# biggity.net
KiCad netlist of a schematic drawn in EAGLE
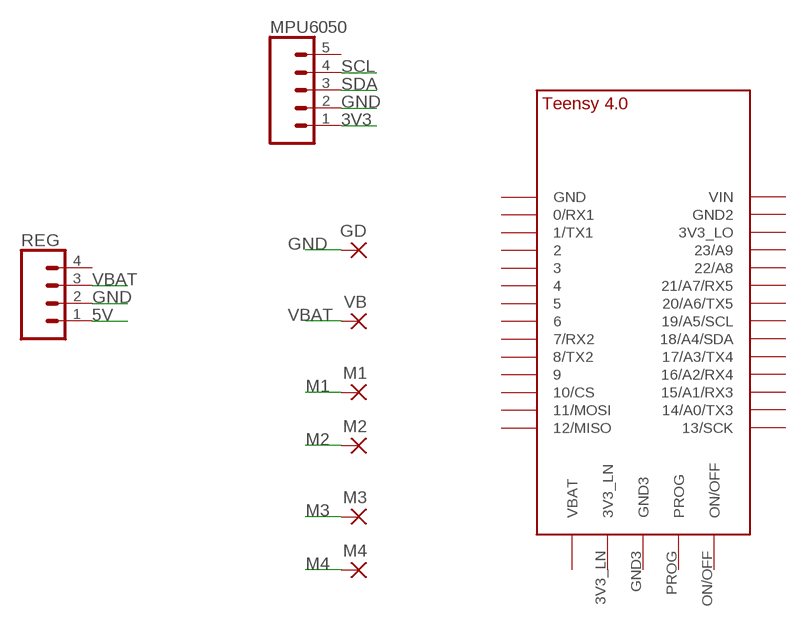
[diagram p0: schematic, sheet 1]

(export (version "E")
  (design (tool "Eeschema 10.0.6"))
  (components
    (comp (ref "GD")
      (value "SMD2")
      (footprint "eagle-import:SMD1,27-2,54")
      (libsource (lib "eagle-import") (part "SMD2"))
    )
    (comp (ref "M1")
      (value "SMD2")
      (footprint "eagle-import:SMD1,27-2,54")
      (libsource (lib "eagle-import") (part "SMD2"))
    )
    (comp (ref "M2")
      (value "SMD2")
      (footprint "eagle-import:SMD1,27-2,54")
      (libsource (lib "eagle-import") (part "SMD2"))
    )
    (comp (ref "M3")
      (value "SMD2")
      (footprint "eagle-import:SMD1,27-2,54")
      (libsource (lib "eagle-import") (part "SMD2"))
    )
    (comp (ref "M4")
      (value "SMD2")
      (footprint "eagle-import:SMD1,27-2,54")
      (libsource (lib "eagle-import") (part "SMD2"))
    )
    (comp (ref "MPU6050")
      (value "CONN_05NO_SILK")
      (footprint "eagle-import:1X05_NO_SILK")
      (libsource (lib "eagle-import") (part "CONN_05NO_SILK"))
    )
    (comp (ref "REG")
      (value "CONN_041X04_NO_SILK")
      (footprint "eagle-import:1X04_NO_SILK")
      (libsource (lib "eagle-import") (part "CONN_041X04_NO_SILK"))
    )
    (comp (ref "U$1")
      (value "TEENSY_4.0")
      (footprint "eagle-import:TEENSY_4.0")
      (libsource (lib "eagle-import") (part "TEENSY_4.0"))
    )
    (comp (ref "VB")
      (value "SMD2")
      (footprint "eagle-import:SMD1,27-2,54")
      (libsource (lib "eagle-import") (part "SMD2"))
    )
  )
  (nets
    (net (code "1") (name "/3V3") (class "Default")
      (node (ref "MPU6050") (pin "1") (pinfunction "1_1") (pintype "passive"))
    )
    (net (code "2") (name "/5V") (class "Default")
      (node (ref "REG") (pin "1") (pinfunction "1_1") (pintype "passive"))
    )
    (net (code "3") (name "/GND") (class "Default")
      (node (ref "GD") (pin "1") (pinfunction "P_1") (pintype "passive"))
      (node (ref "MPU6050") (pin "2") (pinfunction "2_2") (pintype "passive"))
      (node (ref "REG") (pin "2") (pinfunction "2_2") (pintype "passive"))
    )
    (net (code "4") (name "/M1") (class "Default")
      (node (ref "M1") (pin "1") (pinfunction "P_1") (pintype "passive"))
    )
    (net (code "5") (name "/M2") (class "Default")
      (node (ref "M2") (pin "1") (pinfunction "P_1") (pintype "passive"))
    )
    (net (code "6") (name "/M3") (class "Default")
      (node (ref "M3") (pin "1") (pinfunction "P_1") (pintype "passive"))
    )
    (net (code "7") (name "/M4") (class "Default")
      (node (ref "M4") (pin "1") (pinfunction "P_1") (pintype "passive"))
    )
    (net (code "8") (name "/SCL") (class "Default")
      (node (ref "MPU6050") (pin "4") (pinfunction "4_4") (pintype "passive"))
    )
    (net (code "9") (name "/SDA") (class "Default")
      (node (ref "MPU6050") (pin "3") (pinfunction "3_3") (pintype "passive"))
    )
    (net (code "10") (name "/VBAT") (class "Default")
      (node (ref "REG") (pin "3") (pinfunction "3_3") (pintype "passive"))
      (node (ref "VB") (pin "1") (pinfunction "P_1") (pintype "passive"))
    )
    (net (code "11") (name "unconnected-(MPU6050-Pad5)") (class "Default")
      (node (ref "MPU6050") (pin "5") (pinfunction "5_5") (pintype "passive"))
    )
    (net (code "12") (name "unconnected-(REG-Pad4)") (class "Default")
      (node (ref "REG") (pin "4") (pinfunction "4_4") (pintype "passive"))
    )
    (net (code "13") (name "unconnected-(U$1-0{slash}RX1-Pad0{slash}RX)") (class "Default")
      (node (ref "U$1") (pin "0/RX") (pinfunction "0/RX1_0/RX") (pintype "bidirectional"))
    )
    (net (code "14") (name "unconnected-(U$1-1{slash}TX1-Pad1{slash}TX)") (class "Default")
      (node (ref "U$1") (pin "1/TX") (pinfunction "1/TX1_1/TX") (pintype "bidirectional"))
    )
    (net (code "15") (name "unconnected-(U$1-3-Pad3{slash}CANTX)") (class "Default")
      (node (ref "U$1") (pin "3/CANTX") (pinfunction "3_3/CANTX") (pintype "bidirectional"))
    )
    (net (code "16") (name "unconnected-(U$1-4-Pad4{slash}CANRX)") (class "Default")
      (node (ref "U$1") (pin "4/CANRX") (pinfunction "4_4/CANRX") (pintype "bidirectional"))
    )
    (net (code "17") (name "unconnected-(U$1-7{slash}RX2-Pad7)") (class "Default")
      (node (ref "U$1") (pin "7") (pinfunction "7/RX2_7") (pintype "bidirectional"))
    )
    (net (code "18") (name "unconnected-(U$1-8{slash}TX2-Pad8)") (class "Default")
      (node (ref "U$1") (pin "8") (pinfunction "8/TX2_8") (pintype "bidirectional"))
    )
    (net (code "19") (name "unconnected-(U$1-9-Pad9{slash}CS)") (class "Default")
      (node (ref "U$1") (pin "9/CS") (pinfunction "9_9/CS") (pintype "bidirectional"))
    )
    (net (code "20") (name "unconnected-(U$1-14{slash}A0{slash}TX3-Pad14{slash}A0)") (class "Default")
      (node (ref "U$1") (pin "14/A0") (pinfunction "14/A0/TX3_14/A0") (pintype "bidirectional"))
    )
    (net (code "21") (name "unconnected-(U$1-15{slash}A1{slash}RX3-Pad15{slash}A1)") (class "Default")
      (node (ref "U$1") (pin "15/A1") (pinfunction "15/A1/RX3_15/A1") (pintype "bidirectional"))
    )
    (net (code "22") (name "unconnected-(U$1-16{slash}A2{slash}RX4-Pad16{slash}A2)") (class "Default")
      (node (ref "U$1") (pin "16/A2") (pinfunction "16/A2/RX4_16/A2") (pintype "bidirectional"))
    )
    (net (code "23") (name "unconnected-(U$1-17{slash}A3{slash}TX4-Pad17{slash}A3)") (class "Default")
      (node (ref "U$1") (pin "17/A3") (pinfunction "17/A3/TX4_17/A3") (pintype "bidirectional"))
    )
    (net (code "24") (name "unconnected-(U$1-20{slash}A6{slash}TX5-Pad20{slash}A6)") (class "Default")
      (node (ref "U$1") (pin "20/A6") (pinfunction "20/A6/TX5_20/A6") (pintype "bidirectional"))
    )
    (net (code "25") (name "unconnected-(U$1-21{slash}A7{slash}RX5-Pad21{slash}A7)") (class "Default")
      (node (ref "U$1") (pin "21/A7") (pinfunction "21/A7/RX5_21/A7") (pintype "bidirectional"))
    )
    (net (code "26") (name "unconnected-(U$1-Pad2)") (class "Default")
      (node (ref "U$1") (pin "2") (pinfunction "2_2") (pintype "bidirectional"))
    )
    (net (code "27") (name "unconnected-(U$1-Pad3V3_LN)") (class "Default")
      (node (ref "U$1") (pin "3V3_LN") (pinfunction "3V3_LN_3V3_LN") (pintype "bidirectional"))
    )
    (net (code "28") (name "unconnected-(U$1-Pad3V3_LO)") (class "Default")
      (node (ref "U$1") (pin "3V3_LO") (pinfunction "3V3_LO_3V3_LO") (pintype "bidirectional"))
    )
    (net (code "29") (name "unconnected-(U$1-Pad5)") (class "Default")
      (node (ref "U$1") (pin "5") (pinfunction "5_5") (pintype "bidirectional"))
    )
    (net (code "30") (name "unconnected-(U$1-Pad6)") (class "Default")
      (node (ref "U$1") (pin "6") (pinfunction "6_6") (pintype "bidirectional"))
    )
    (net (code "31") (name "unconnected-(U$1-Pad10{slash}CS)") (class "Default")
      (node (ref "U$1") (pin "10/CS") (pinfunction "10/CS_10/CS") (pintype "bidirectional"))
    )
    (net (code "32") (name "unconnected-(U$1-Pad11{slash}MOSI)") (class "Default")
      (node (ref "U$1") (pin "11/MOSI") (pinfunction "11/MOSI_11/MOSI") (pintype "bidirectional"))
    )
    (net (code "33") (name "unconnected-(U$1-Pad12{slash}MISO)") (class "Default")
      (node (ref "U$1") (pin "12/MISO") (pinfunction "12/MISO_12/MISO") (pintype "bidirectional"))
    )
    (net (code "34") (name "unconnected-(U$1-Pad13{slash}SCK)") (class "Default")
      (node (ref "U$1") (pin "13/SCK") (pinfunction "13/SCK_13/SCK") (pintype "bidirectional"))
    )
    (net (code "35") (name "unconnected-(U$1-Pad18{slash}A4{slash}SDA)") (class "Default")
      (node (ref "U$1") (pin "18/A4/SDA") (pinfunction "18/A4/SDA_18/A4/SDA") (pintype "bidirectional"))
    )
    (net (code "36") (name "unconnected-(U$1-Pad19{slash}A5{slash}SCL)") (class "Default")
      (node (ref "U$1") (pin "19/A5/SCL") (pinfunction "19/A5/SCL_19/A5/SCL") (pintype "bidirectional"))
    )
    (net (code "37") (name "unconnected-(U$1-Pad22{slash}A8)") (class "Default")
      (node (ref "U$1") (pin "22/A8") (pinfunction "22/A8_22/A8") (pintype "bidirectional"))
    )
    (net (code "38") (name "unconnected-(U$1-Pad23{slash}A9)") (class "Default")
      (node (ref "U$1") (pin "23/A9") (pinfunction "23/A9_23/A9") (pintype "bidirectional"))
    )
    (net (code "39") (name "unconnected-(U$1-PadGND)") (class "Default")
      (node (ref "U$1") (pin "GND") (pinfunction "GND_GND") (pintype "bidirectional"))
    )
    (net (code "40") (name "unconnected-(U$1-PadGND2)") (class "Default")
      (node (ref "U$1") (pin "GND2") (pinfunction "GND2_GND2") (pintype "bidirectional"))
    )
    (net (code "41") (name "unconnected-(U$1-PadGND3)") (class "Default")
      (node (ref "U$1") (pin "GND3") (pinfunction "GND3_GND3") (pintype "bidirectional"))
    )
    (net (code "42") (name "unconnected-(U$1-PadON{slash}OFF)") (class "Default")
      (node (ref "U$1") (pin "ON/OFF") (pinfunction "ON/OFF_ON/OFF") (pintype "bidirectional"))
    )
    (net (code "43") (name "unconnected-(U$1-PadPROG)") (class "Default")
      (node (ref "U$1") (pin "PROG") (pinfunction "PROG_PROG") (pintype "bidirectional"))
    )
    (net (code "44") (name "unconnected-(U$1-PadVIN)") (class "Default")
      (node (ref "U$1") (pin "VIN") (pinfunction "VIN_VIN") (pintype "bidirectional"))
    )
    (net (code "45") (name "unconnected-(U$1-VBAT-PadVBAT\\)") (class "Default")
      (node (ref "U$1") (pin "VBAT\\") (pinfunction "VBAT_VBAT\\") (pintype "bidirectional"))
    )
  )
)
